# con_connector.net
KiCad netlist of a schematic drawn in EAGLE
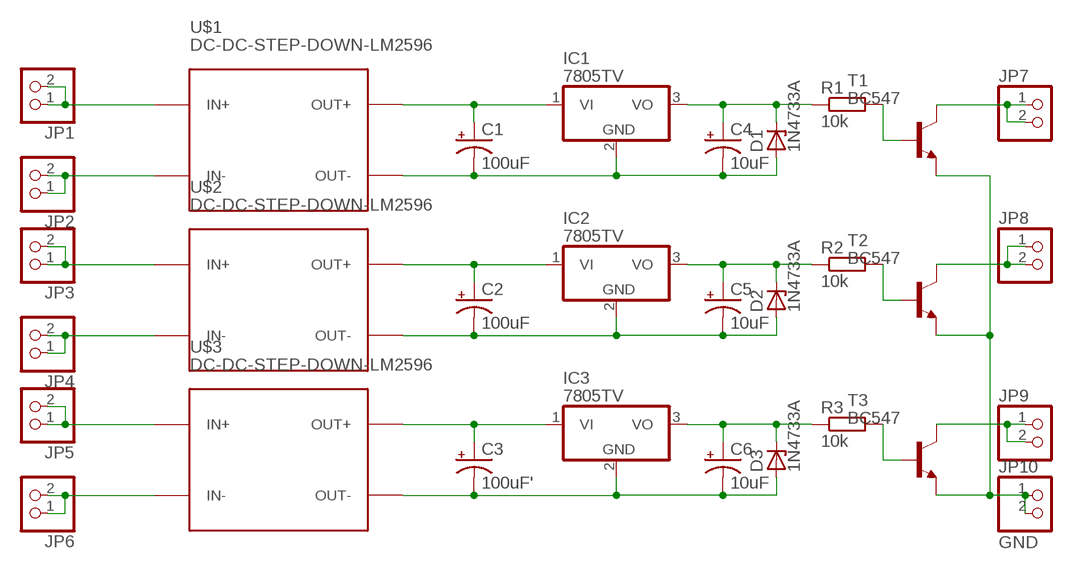
[diagram p0: schematic, sheet 1]

(export (version "E")
  (design (tool "Eeschema 10.0.6"))
  (components
    (comp (ref "C1")
      (value "100uF")
      (footprint "eagle-import:E2,5-7")
      (libsource (lib "eagle-import") (part "CPOL-USE2.5-7"))
    )
    (comp (ref "C2")
      (value "100uF")
      (footprint "eagle-import:E2,5-7")
      (libsource (lib "eagle-import") (part "CPOL-USE2.5-7"))
    )
    (comp (ref "C3")
      (value "100uF'")
      (footprint "eagle-import:E2,5-7")
      (libsource (lib "eagle-import") (part "CPOL-USE2.5-7"))
    )
    (comp (ref "C4")
      (value "10uF")
      (footprint "eagle-import:E2,5-6")
      (libsource (lib "eagle-import") (part "CPOL-USE2.5-6"))
    )
    (comp (ref "C5")
      (value "10uF")
      (footprint "eagle-import:E2,5-6")
      (libsource (lib "eagle-import") (part "CPOL-USE2.5-6"))
    )
    (comp (ref "C6")
      (value "10uF")
      (footprint "eagle-import:E2,5-6")
      (libsource (lib "eagle-import") (part "CPOL-USE2.5-6"))
    )
    (comp (ref "D1")
      (value "1N4733A")
      (footprint "eagle-import:DO41Z10")
      (libsource (lib "eagle-import") (part "1N4728"))
    )
    (comp (ref "D2")
      (value "1N4733A")
      (footprint "eagle-import:DO41Z10")
      (libsource (lib "eagle-import") (part "1N4728"))
    )
    (comp (ref "D3")
      (value "1N4733A")
      (footprint "eagle-import:DO41Z10")
      (libsource (lib "eagle-import") (part "1N4728"))
    )
    (comp (ref "IC1")
      (value "7805TV")
      (footprint "eagle-import:TO220V")
      (libsource (lib "eagle-import") (part "78TV05"))
    )
    (comp (ref "IC2")
      (value "7805TV")
      (footprint "eagle-import:TO220V")
      (libsource (lib "eagle-import") (part "78TV05"))
    )
    (comp (ref "IC3")
      (value "7805TV")
      (footprint "eagle-import:TO220V")
      (libsource (lib "eagle-import") (part "78TV05"))
    )
    (comp (ref "JP1")
      (value "PINHD-1X2")
      (footprint "eagle-import:1X02")
      (libsource (lib "eagle-import") (part "PINHD-1X2"))
    )
    (comp (ref "JP2")
      (value "PINHD-1X2")
      (footprint "eagle-import:1X02")
      (libsource (lib "eagle-import") (part "PINHD-1X2"))
    )
    (comp (ref "JP3")
      (value "PINHD-1X2")
      (footprint "eagle-import:1X02")
      (libsource (lib "eagle-import") (part "PINHD-1X2"))
    )
    (comp (ref "JP4")
      (value "PINHD-1X2")
      (footprint "eagle-import:1X02")
      (libsource (lib "eagle-import") (part "PINHD-1X2"))
    )
    (comp (ref "JP5")
      (value "PINHD-1X2")
      (footprint "eagle-import:1X02")
      (libsource (lib "eagle-import") (part "PINHD-1X2"))
    )
    (comp (ref "JP6")
      (value "PINHD-1X2")
      (footprint "eagle-import:1X02")
      (libsource (lib "eagle-import") (part "PINHD-1X2"))
    )
    (comp (ref "JP7")
      (value "PINHD-1X2")
      (footprint "eagle-import:1X02")
      (libsource (lib "eagle-import") (part "PINHD-1X2"))
    )
    (comp (ref "JP8")
      (value "PINHD-1X2")
      (footprint "eagle-import:1X02")
      (libsource (lib "eagle-import") (part "PINHD-1X2"))
    )
    (comp (ref "JP9")
      (value "PINHD-1X2")
      (footprint "eagle-import:1X02")
      (libsource (lib "eagle-import") (part "PINHD-1X2"))
    )
    (comp (ref "JP10")
      (value "GND")
      (footprint "eagle-import:1X02")
      (libsource (lib "eagle-import") (part "PINHD-1X2"))
    )
    (comp (ref "R1")
      (value "10k")
      (footprint "eagle-import:0207_12")
      (libsource (lib "eagle-import") (part "R-EU_0207/12"))
    )
    (comp (ref "R2")
      (value "10k")
      (footprint "eagle-import:0207_12")
      (libsource (lib "eagle-import") (part "R-EU_0207/12"))
    )
    (comp (ref "R3")
      (value "10k")
      (footprint "eagle-import:0207_12")
      (libsource (lib "eagle-import") (part "R-EU_0207/12"))
    )
    (comp (ref "T1")
      (value "BC547")
      (footprint "eagle-import:TO92")
      (libsource (lib "eagle-import") (part "BC547"))
    )
    (comp (ref "T2")
      (value "BC547")
      (footprint "eagle-import:TO92")
      (libsource (lib "eagle-import") (part "BC547"))
    )
    (comp (ref "T3")
      (value "BC547")
      (footprint "eagle-import:TO92")
      (libsource (lib "eagle-import") (part "BC547"))
    )
    (comp (ref "U$1")
      (value "DC-DC-STEP-DOWN-LM2596")
      (footprint "eagle-import:DC-DC-STEP-DOWN-LM2596")
      (libsource (lib "eagle-import") (part "DC-DC-STEP-DOWN-LM2596"))
    )
    (comp (ref "U$2")
      (value "DC-DC-STEP-DOWN-LM2596")
      (footprint "eagle-import:DC-DC-STEP-DOWN-LM2596")
      (libsource (lib "eagle-import") (part "DC-DC-STEP-DOWN-LM2596"))
    )
    (comp (ref "U$3")
      (value "DC-DC-STEP-DOWN-LM2596")
      (footprint "eagle-import:DC-DC-STEP-DOWN-LM2596")
      (libsource (lib "eagle-import") (part "DC-DC-STEP-DOWN-LM2596"))
    )
  )
  (nets
    (net (code "1") (name "Net-(IC1-GND)") (class "Default")
      (node (ref "C1") (pin "-") (pinfunction "-_-") (pintype "passive"))
      (node (ref "C4") (pin "-") (pinfunction "-_-") (pintype "passive"))
      (node (ref "D1") (pin "A") (pinfunction "A_A") (pintype "passive"))
      (node (ref "IC1") (pin "2") (pinfunction "GND_2") (pintype "passive"))
      (node (ref "U$1") (pin "OUT-") (pinfunction "OUT-_OUT-") (pintype "bidirectional"))
    )
    (net (code "2") (name "Net-(IC1-VI)") (class "Default")
      (node (ref "C1") (pin "+") (pinfunction "+_+") (pintype "passive"))
      (node (ref "IC1") (pin "1") (pinfunction "VI_1") (pintype "input"))
      (node (ref "U$1") (pin "OUT+") (pinfunction "OUT+_OUT+") (pintype "bidirectional"))
    )
    (net (code "3") (name "Net-(IC1-VO)") (class "Default")
      (node (ref "C4") (pin "+") (pinfunction "+_+") (pintype "passive"))
      (node (ref "D1") (pin "C") (pinfunction "C_C") (pintype "passive"))
      (node (ref "IC1") (pin "3") (pinfunction "VO_3") (pintype "passive"))
      (node (ref "R1") (pin "1") (pinfunction "1_1") (pintype "passive"))
    )
    (net (code "4") (name "Net-(IC2-GND)") (class "Default")
      (node (ref "C2") (pin "-") (pinfunction "-_-") (pintype "passive"))
      (node (ref "C5") (pin "-") (pinfunction "-_-") (pintype "passive"))
      (node (ref "D2") (pin "A") (pinfunction "A_A") (pintype "passive"))
      (node (ref "IC2") (pin "2") (pinfunction "GND_2") (pintype "passive"))
      (node (ref "U$2") (pin "OUT-") (pinfunction "OUT-_OUT-") (pintype "bidirectional"))
    )
    (net (code "5") (name "Net-(IC2-VI)") (class "Default")
      (node (ref "C2") (pin "+") (pinfunction "+_+") (pintype "passive"))
      (node (ref "IC2") (pin "1") (pinfunction "VI_1") (pintype "input"))
      (node (ref "U$2") (pin "OUT+") (pinfunction "OUT+_OUT+") (pintype "bidirectional"))
    )
    (net (code "6") (name "Net-(IC2-VO)") (class "Default")
      (node (ref "C5") (pin "+") (pinfunction "+_+") (pintype "passive"))
      (node (ref "D2") (pin "C") (pinfunction "C_C") (pintype "passive"))
      (node (ref "IC2") (pin "3") (pinfunction "VO_3") (pintype "passive"))
      (node (ref "R2") (pin "1") (pinfunction "1_1") (pintype "passive"))
    )
    (net (code "7") (name "Net-(IC3-GND)") (class "Default")
      (node (ref "C3") (pin "-") (pinfunction "-_-") (pintype "passive"))
      (node (ref "C6") (pin "-") (pinfunction "-_-") (pintype "passive"))
      (node (ref "D3") (pin "A") (pinfunction "A_A") (pintype "passive"))
      (node (ref "IC3") (pin "2") (pinfunction "GND_2") (pintype "passive"))
      (node (ref "U$3") (pin "OUT-") (pinfunction "OUT-_OUT-") (pintype "bidirectional"))
    )
    (net (code "8") (name "Net-(IC3-VI)") (class "Default")
      (node (ref "C3") (pin "+") (pinfunction "+_+") (pintype "passive"))
      (node (ref "IC3") (pin "1") (pinfunction "VI_1") (pintype "input"))
      (node (ref "U$3") (pin "OUT+") (pinfunction "OUT+_OUT+") (pintype "bidirectional"))
    )
    (net (code "9") (name "Net-(IC3-VO)") (class "Default")
      (node (ref "C6") (pin "+") (pinfunction "+_+") (pintype "passive"))
      (node (ref "D3") (pin "C") (pinfunction "C_C") (pintype "passive"))
      (node (ref "IC3") (pin "3") (pinfunction "VO_3") (pintype "passive"))
      (node (ref "R3") (pin "1") (pinfunction "1_1") (pintype "passive"))
    )
    (net (code "10") (name "Net-(JP1-Pad1)") (class "Default")
      (node (ref "JP1") (pin "1") (pinfunction "1_1") (pintype "passive"))
      (node (ref "JP1") (pin "2") (pinfunction "2_2") (pintype "passive"))
      (node (ref "U$1") (pin "IN+") (pinfunction "IN+_IN+") (pintype "bidirectional"))
    )
    (net (code "11") (name "Net-(JP2-Pad1)") (class "Default")
      (node (ref "JP2") (pin "1") (pinfunction "1_1") (pintype "passive"))
      (node (ref "JP2") (pin "2") (pinfunction "2_2") (pintype "passive"))
      (node (ref "U$1") (pin "IN-") (pinfunction "IN-_IN-") (pintype "bidirectional"))
    )
    (net (code "12") (name "Net-(JP3-Pad1)") (class "Default")
      (node (ref "JP3") (pin "1") (pinfunction "1_1") (pintype "passive"))
      (node (ref "JP3") (pin "2") (pinfunction "2_2") (pintype "passive"))
      (node (ref "U$2") (pin "IN+") (pinfunction "IN+_IN+") (pintype "bidirectional"))
    )
    (net (code "13") (name "Net-(JP4-Pad1)") (class "Default")
      (node (ref "JP4") (pin "1") (pinfunction "1_1") (pintype "passive"))
      (node (ref "JP4") (pin "2") (pinfunction "2_2") (pintype "passive"))
      (node (ref "U$2") (pin "IN-") (pinfunction "IN-_IN-") (pintype "bidirectional"))
    )
    (net (code "14") (name "Net-(JP5-Pad1)") (class "Default")
      (node (ref "JP5") (pin "1") (pinfunction "1_1") (pintype "passive"))
      (node (ref "JP5") (pin "2") (pinfunction "2_2") (pintype "passive"))
      (node (ref "U$3") (pin "IN+") (pinfunction "IN+_IN+") (pintype "bidirectional"))
    )
    (net (code "15") (name "Net-(JP6-Pad1)") (class "Default")
      (node (ref "JP6") (pin "1") (pinfunction "1_1") (pintype "passive"))
      (node (ref "JP6") (pin "2") (pinfunction "2_2") (pintype "passive"))
      (node (ref "U$3") (pin "IN-") (pinfunction "IN-_IN-") (pintype "bidirectional"))
    )
    (net (code "16") (name "Net-(T1-B)") (class "Default")
      (node (ref "R1") (pin "2") (pinfunction "2_2") (pintype "passive"))
      (node (ref "T1") (pin "2") (pinfunction "B_2") (pintype "passive"))
    )
    (net (code "17") (name "Net-(T1-C)") (class "Default")
      (node (ref "JP7") (pin "1") (pinfunction "1_1") (pintype "passive"))
      (node (ref "JP7") (pin "2") (pinfunction "2_2") (pintype "passive"))
      (node (ref "T1") (pin "3") (pinfunction "C_3") (pintype "passive"))
    )
    (net (code "18") (name "Net-(T1-E)") (class "Default")
      (node (ref "JP10") (pin "1") (pinfunction "1_1") (pintype "passive"))
      (node (ref "JP10") (pin "2") (pinfunction "2_2") (pintype "passive"))
      (node (ref "T1") (pin "1") (pinfunction "E_1") (pintype "passive"))
      (node (ref "T2") (pin "1") (pinfunction "E_1") (pintype "passive"))
      (node (ref "T3") (pin "1") (pinfunction "E_1") (pintype "passive"))
    )
    (net (code "19") (name "Net-(T2-B)") (class "Default")
      (node (ref "R2") (pin "2") (pinfunction "2_2") (pintype "passive"))
      (node (ref "T2") (pin "2") (pinfunction "B_2") (pintype "passive"))
    )
    (net (code "20") (name "Net-(T2-C)") (class "Default")
      (node (ref "JP8") (pin "1") (pinfunction "1_1") (pintype "passive"))
      (node (ref "JP8") (pin "2") (pinfunction "2_2") (pintype "passive"))
      (node (ref "T2") (pin "3") (pinfunction "C_3") (pintype "passive"))
    )
    (net (code "21") (name "Net-(T3-B)") (class "Default")
      (node (ref "R3") (pin "2") (pinfunction "2_2") (pintype "passive"))
      (node (ref "T3") (pin "2") (pinfunction "B_2") (pintype "passive"))
    )
    (net (code "22") (name "Net-(T3-C)") (class "Default")
      (node (ref "JP9") (pin "1") (pinfunction "1_1") (pintype "passive"))
      (node (ref "JP9") (pin "2") (pinfunction "2_2") (pintype "passive"))
      (node (ref "T3") (pin "3") (pinfunction "C_3") (pintype "passive"))
    )
  )
)
